# gainster2.net
KiCad netlist of a schematic drawn in EAGLE
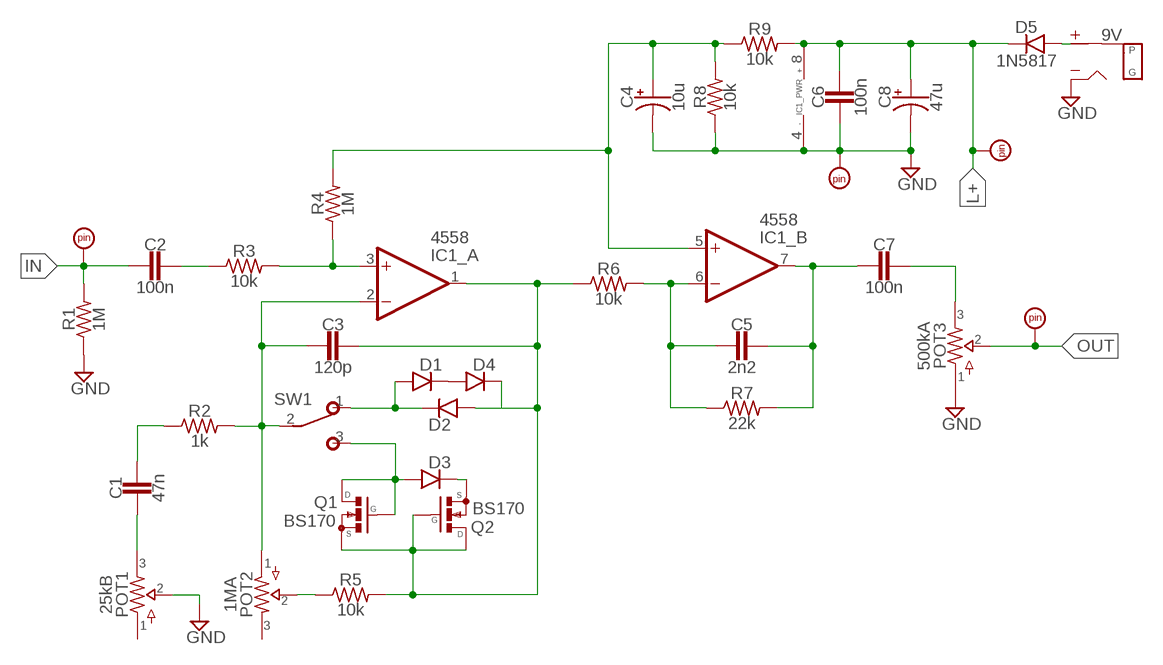
[diagram p0: schematic, sheet 1]

(export (version "E")
  (design (tool "Eeschema 10.0.6"))
  (components
    (comp (ref "9V")
      (value "DC_MONO")
      (footprint "eagle-import:DC")
      (libsource (lib "eagle-import") (part "DC_MONO"))
    )
    (comp (ref "C1")
      (value "47n")
      (footprint "eagle-import:050X030_025_2")
      (libsource (lib "eagle-import") (part "CER/FILM2"))
    )
    (comp (ref "C2")
      (value "100n")
      (footprint "eagle-import:050X030_025_2")
      (libsource (lib "eagle-import") (part "CER/FILM2"))
    )
    (comp (ref "C3")
      (value "120p")
      (footprint "eagle-import:050X030_025_2")
      (libsource (lib "eagle-import") (part "CER/FILM2"))
    )
    (comp (ref "C4")
      (value "10u")
      (footprint "eagle-import:050_020_1")
      (libsource (lib "eagle-import") (part "0501"))
    )
    (comp (ref "C5")
      (value "2n2")
      (footprint "eagle-import:050X030_025_2")
      (libsource (lib "eagle-import") (part "CER/FILM2"))
    )
    (comp (ref "C6")
      (value "100n")
      (footprint "eagle-import:050X030_025_2")
      (libsource (lib "eagle-import") (part "CER/FILM2"))
    )
    (comp (ref "C7")
      (value "100n")
      (footprint "eagle-import:050X030_025_2")
      (libsource (lib "eagle-import") (part "CER/FILM2"))
    )
    (comp (ref "C8")
      (value "47u")
      (footprint "eagle-import:050_020_1")
      (libsource (lib "eagle-import") (part "0501"))
    )
    (comp (ref "D1")
      (value "DO41.2")
      (footprint "eagle-import:DO41-2")
      (libsource (lib "eagle-import") (part "DO41.2"))
    )
    (comp (ref "D2")
      (value "DO41.2")
      (footprint "eagle-import:DO41-2")
      (libsource (lib "eagle-import") (part "DO41.2"))
    )
    (comp (ref "D3")
      (value "DO41.2")
      (footprint "eagle-import:DO41-2")
      (libsource (lib "eagle-import") (part "DO41.2"))
    )
    (comp (ref "D4")
      (value "DO41.2")
      (footprint "eagle-import:DO41-2")
      (libsource (lib "eagle-import") (part "DO41.2"))
    )
    (comp (ref "D5")
      (value "1N5817")
      (footprint "eagle-import:DO35-3")
      (libsource (lib "eagle-import") (part "DO35.3"))
    )
    (comp (ref "IC1")
      (value "4558")
      (footprint "eagle-import:DIL08")
      (libsource (lib "eagle-import") (part "DUALTH"))
    )
    (comp (ref "IN")
      (value "PADSQR")
      (footprint "eagle-import:SQUARE")
      (libsource (lib "eagle-import") (part "PADSQR"))
    )
    (comp (ref "LED")
      (value "PADSQR")
      (footprint "eagle-import:SQUARE")
      (libsource (lib "eagle-import") (part "PADSQR"))
    )
    (comp (ref "OUT")
      (value "PADSQR")
      (footprint "eagle-import:SQUARE")
      (libsource (lib "eagle-import") (part "PADSQR"))
    )
    (comp (ref "PAD2")
      (value "PADRND")
      (footprint "eagle-import:ROUND")
      (libsource (lib "eagle-import") (part "PADRND"))
    )
    (comp (ref "POT1")
      (value "25kB")
      (footprint "eagle-import:16MM")
      (libsource (lib "eagle-import") (part "POTS16MM"))
    )
    (comp (ref "POT2")
      (value "1MA")
      (footprint "eagle-import:16MM")
      (libsource (lib "eagle-import") (part "POTS16MM"))
    )
    (comp (ref "POT3")
      (value "500kA")
      (footprint "eagle-import:16MM")
      (libsource (lib "eagle-import") (part "POTS16MM"))
    )
    (comp (ref "Q1")
      (value "BS170")
      (footprint "eagle-import:SOT54ES")
      (libsource (lib "eagle-import") (part "BS170"))
    )
    (comp (ref "Q2")
      (value "BS170")
      (footprint "eagle-import:SOT54ES")
      (libsource (lib "eagle-import") (part "BS170"))
    )
    (comp (ref "R1")
      (value "1M")
      (footprint "eagle-import:R0207_3")
      (libsource (lib "eagle-import") (part "R_.3B"))
    )
    (comp (ref "R2")
      (value "1k")
      (footprint "eagle-import:R0207_3")
      (libsource (lib "eagle-import") (part "R_.3B"))
    )
    (comp (ref "R3")
      (value "10k")
      (footprint "eagle-import:R0207_3")
      (libsource (lib "eagle-import") (part "R_.3B"))
    )
    (comp (ref "R4")
      (value "1M")
      (footprint "eagle-import:R0207_3")
      (libsource (lib "eagle-import") (part "R_.3B"))
    )
    (comp (ref "R5")
      (value "10k")
      (footprint "eagle-import:R0207_3")
      (libsource (lib "eagle-import") (part "R_.3B"))
    )
    (comp (ref "R6")
      (value "10k")
      (footprint "eagle-import:R0207_3")
      (libsource (lib "eagle-import") (part "R_.3B"))
    )
    (comp (ref "R7")
      (value "22k")
      (footprint "eagle-import:R0207_3")
      (libsource (lib "eagle-import") (part "R_.3B"))
    )
    (comp (ref "R8")
      (value "10k")
      (footprint "eagle-import:R0207_3")
      (libsource (lib "eagle-import") (part "R_.3B"))
    )
    (comp (ref "R9")
      (value "10k")
      (footprint "eagle-import:R0207_3")
      (libsource (lib "eagle-import") (part "R_.3B"))
    )
    (comp (ref "SW1")
      (value "SPDT")
      (footprint "eagle-import:M9040P")
      (libsource (lib "eagle-import") (part "SPDT"))
    )
  )
  (nets
    (net (code "1") (name "GND") (class "Default")
      (node (ref "9V") (pin "S") (pinfunction "SLEEVE_S") (pintype "passive"))
      (node (ref "C4") (pin "-") (pinfunction "-_-") (pintype "passive"))
      (node (ref "C6") (pin "2") (pinfunction "2_2") (pintype "passive"))
      (node (ref "C8") (pin "-") (pinfunction "-_-") (pintype "passive"))
      (node (ref "IC1") (pin "4") (pinfunction "V-_4") (pintype "power_in"))
      (node (ref "PAD2") (pin "1") (pinfunction "P$1_1") (pintype "bidirectional"))
      (node (ref "POT1") (pin "2") (pinfunction "2_2") (pintype "passive"))
      (node (ref "POT3") (pin "1") (pinfunction "1_1") (pintype "passive"))
      (node (ref "R1") (pin "1") (pinfunction "1_1") (pintype "passive"))
      (node (ref "R8") (pin "1") (pinfunction "1_1") (pintype "passive"))
    )
    (net (code "2") (name "IN") (class "Default")
      (node (ref "C2") (pin "2") (pinfunction "2_2") (pintype "passive"))
      (node (ref "IN") (pin "1") (pinfunction "P$1_1") (pintype "bidirectional"))
      (node (ref "R1") (pin "2") (pinfunction "2_2") (pintype "passive"))
    )
    (net (code "3") (name "L+") (class "Default")
      (node (ref "C6") (pin "1") (pinfunction "1_1") (pintype "passive"))
      (node (ref "C8") (pin "+") (pinfunction "+_+") (pintype "passive"))
      (node (ref "D5") (pin "C") (pinfunction "C_C") (pintype "passive"))
      (node (ref "IC1") (pin "8") (pinfunction "V+_8") (pintype "power_in"))
      (node (ref "LED") (pin "1") (pinfunction "P$1_1") (pintype "bidirectional"))
      (node (ref "R9") (pin "2") (pinfunction "2_2") (pintype "passive"))
    )
    (net (code "4") (name "Net-(9V-TIP)") (class "Default")
      (node (ref "9V") (pin "T") (pinfunction "TIP_T") (pintype "passive"))
      (node (ref "D5") (pin "A") (pinfunction "A_A") (pintype "passive"))
    )
    (net (code "5") (name "Net-(C1-Pad1)") (class "Default")
      (node (ref "C1") (pin "1") (pinfunction "1_1") (pintype "passive"))
      (node (ref "R2") (pin "1") (pinfunction "1_1") (pintype "passive"))
    )
    (net (code "6") (name "Net-(C1-Pad2)") (class "Default")
      (node (ref "C1") (pin "2") (pinfunction "2_2") (pintype "passive"))
      (node (ref "POT1") (pin "3") (pinfunction "3_3") (pintype "passive"))
    )
    (net (code "7") (name "Net-(C2-Pad1)") (class "Default")
      (node (ref "C2") (pin "1") (pinfunction "1_1") (pintype "passive"))
      (node (ref "R3") (pin "1") (pinfunction "1_1") (pintype "passive"))
    )
    (net (code "8") (name "Net-(C7-Pad1)") (class "Default")
      (node (ref "C7") (pin "1") (pinfunction "1_1") (pintype "passive"))
      (node (ref "POT3") (pin "3") (pinfunction "3_3") (pintype "passive"))
    )
    (net (code "9") (name "Net-(D1-PadC)") (class "Default")
      (node (ref "D1") (pin "C") (pinfunction "C_C") (pintype "passive"))
      (node (ref "D4") (pin "A") (pinfunction "A_A") (pintype "passive"))
    )
    (net (code "10") (name "Net-(D3-PadC)") (class "Default")
      (node (ref "D3") (pin "C") (pinfunction "C_C") (pintype "passive"))
      (node (ref "Q2") (pin "S") (pinfunction "S_S") (pintype "passive"))
    )
    (net (code "11") (name "Net-(IC1A-+IN)") (class "Default")
      (node (ref "IC1") (pin "3") (pinfunction "+IN_3") (pintype "input"))
      (node (ref "R3") (pin "2") (pinfunction "2_2") (pintype "passive"))
      (node (ref "R4") (pin "1") (pinfunction "1_1") (pintype "passive"))
    )
    (net (code "12") (name "Net-(IC1A--IN)") (class "Default")
      (node (ref "C3") (pin "2") (pinfunction "2_2") (pintype "passive"))
      (node (ref "IC1") (pin "2") (pinfunction "-IN_2") (pintype "input"))
      (node (ref "POT2") (pin "1") (pinfunction "1_1") (pintype "passive"))
      (node (ref "R2") (pin "2") (pinfunction "2_2") (pintype "passive"))
      (node (ref "SW1") (pin "2") (pinfunction "P_2") (pintype "passive"))
    )
    (net (code "13") (name "Net-(IC1A-OUT)") (class "Default")
      (node (ref "C3") (pin "1") (pinfunction "1_1") (pintype "passive"))
      (node (ref "D2") (pin "A") (pinfunction "A_A") (pintype "passive"))
      (node (ref "D4") (pin "C") (pinfunction "C_C") (pintype "passive"))
      (node (ref "IC1") (pin "1") (pinfunction "OUT_1") (pintype "output"))
      (node (ref "Q1") (pin "S") (pinfunction "S_S") (pintype "passive"))
      (node (ref "Q2") (pin "D") (pinfunction "D_D") (pintype "passive"))
      (node (ref "Q2") (pin "G") (pinfunction "G_G") (pintype "passive"))
      (node (ref "R5") (pin "2") (pinfunction "2_2") (pintype "passive"))
      (node (ref "R6") (pin "1") (pinfunction "1_1") (pintype "passive"))
    )
    (net (code "14") (name "Net-(IC1B-+IN)") (class "Default")
      (node (ref "C4") (pin "+") (pinfunction "+_+") (pintype "passive"))
      (node (ref "IC1") (pin "5") (pinfunction "+IN_5") (pintype "input"))
      (node (ref "R4") (pin "2") (pinfunction "2_2") (pintype "passive"))
      (node (ref "R8") (pin "2") (pinfunction "2_2") (pintype "passive"))
      (node (ref "R9") (pin "1") (pinfunction "1_1") (pintype "passive"))
    )
    (net (code "15") (name "Net-(IC1B--IN)") (class "Default")
      (node (ref "C5") (pin "2") (pinfunction "2_2") (pintype "passive"))
      (node (ref "IC1") (pin "6") (pinfunction "-IN_6") (pintype "input"))
      (node (ref "R6") (pin "2") (pinfunction "2_2") (pintype "passive"))
      (node (ref "R7") (pin "1") (pinfunction "1_1") (pintype "passive"))
    )
    (net (code "16") (name "Net-(IC1B-OUT)") (class "Default")
      (node (ref "C5") (pin "1") (pinfunction "1_1") (pintype "passive"))
      (node (ref "C7") (pin "2") (pinfunction "2_2") (pintype "passive"))
      (node (ref "IC1") (pin "7") (pinfunction "OUT_7") (pintype "output"))
      (node (ref "R7") (pin "2") (pinfunction "2_2") (pintype "passive"))
    )
    (net (code "17") (name "Net-(POT2-Pad2)") (class "Default")
      (node (ref "POT2") (pin "2") (pinfunction "2_2") (pintype "passive"))
      (node (ref "R5") (pin "1") (pinfunction "1_1") (pintype "passive"))
    )
    (net (code "18") (name "Net-(SW1-O)") (class "Default")
      (node (ref "D1") (pin "A") (pinfunction "A_A") (pintype "passive"))
      (node (ref "D2") (pin "C") (pinfunction "C_C") (pintype "passive"))
      (node (ref "SW1") (pin "1") (pinfunction "O_1") (pintype "passive"))
    )
    (net (code "19") (name "Net-(SW1-S)") (class "Default")
      (node (ref "D3") (pin "A") (pinfunction "A_A") (pintype "passive"))
      (node (ref "Q1") (pin "D") (pinfunction "D_D") (pintype "passive"))
      (node (ref "Q1") (pin "G") (pinfunction "G_G") (pintype "passive"))
      (node (ref "SW1") (pin "3") (pinfunction "S_3") (pintype "passive"))
    )
    (net (code "20") (name "OUT") (class "Default")
      (node (ref "OUT") (pin "1") (pinfunction "P$1_1") (pintype "bidirectional"))
      (node (ref "POT3") (pin "2") (pinfunction "2_2") (pintype "passive"))
    )
    (net (code "21") (name "unconnected-(POT1-Pad1)") (class "Default")
      (node (ref "POT1") (pin "1") (pinfunction "1_1") (pintype "passive"))
    )
    (net (code "22") (name "unconnected-(POT2-Pad3)") (class "Default")
      (node (ref "POT2") (pin "3") (pinfunction "3_3") (pintype "passive"))
    )
  )
)
